# Filter.net
KiCad netlist of a schematic drawn in Altium Designer
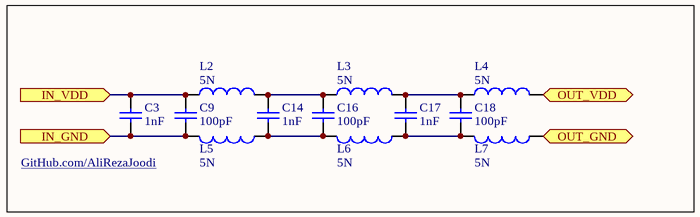
[diagram p0: Filter.SchDoc]

(export (version "E")
  (design (tool "Eeschema 10.0.6"))
  (components
    (comp (ref "C3")
      (value "1nF")
      (footprint "CAPNTO2.54-3.56x2.03")
      (description "Capacitor")
      (fields (field (name "MANUFACTURER") "Generic Components") (field (name "PUBLISHER") "Altium Limited"))
      (libsource (lib "Miscellaneous Devices") (part "Cap"))
    )
    (comp (ref "C9")
      (value "100pF")
      (footprint "CAPNTO2.54-3.56x2.03")
      (description "Capacitor")
      (fields (field (name "MANUFACTURER") "Generic Components") (field (name "PUBLISHER") "Altium Limited"))
      (libsource (lib "Miscellaneous Devices") (part "Cap"))
    )
    (comp (ref "C14")
      (value "1nF")
      (footprint "CAPNTO2.54-3.56x2.03")
      (description "Capacitor")
      (fields (field (name "MANUFACTURER") "Generic Components") (field (name "PUBLISHER") "Altium Limited"))
      (libsource (lib "Miscellaneous Devices") (part "Cap"))
    )
    (comp (ref "C16")
      (value "100pF")
      (footprint "CAPNTO2.54-3.56x2.03")
      (description "Capacitor")
      (fields (field (name "MANUFACTURER") "Generic Components") (field (name "PUBLISHER") "Altium Limited"))
      (libsource (lib "Miscellaneous Devices") (part "Cap"))
    )
    (comp (ref "C17")
      (value "1nF")
      (footprint "CAPNTO2.54-3.56x2.03")
      (description "Capacitor")
      (fields (field (name "MANUFACTURER") "Generic Components") (field (name "PUBLISHER") "Altium Limited"))
      (libsource (lib "Miscellaneous Devices") (part "Cap"))
    )
    (comp (ref "C18")
      (value "100pF")
      (footprint "CAPNTO2.54-3.56x2.03")
      (description "Capacitor")
      (fields (field (name "MANUFACTURER") "Generic Components") (field (name "PUBLISHER") "Altium Limited"))
      (libsource (lib "Miscellaneous Devices") (part "Cap"))
    )
    (comp (ref "L2")
      (value "5N")
      (footprint "CAPPR5-6.3x11")
      (description "Inductor")
      (fields (field (name "MANUFACTURER") "Generic Components") (field (name "PUBLISHER") "Altium Limited"))
      (libsource (lib "my Libraries") (part "Inductor"))
    )
    (comp (ref "L3")
      (value "5N")
      (footprint "CAPPR5-6.3x11")
      (description "Inductor")
      (fields (field (name "MANUFACTURER") "Generic Components") (field (name "PUBLISHER") "Altium Limited"))
      (libsource (lib "my Libraries") (part "Inductor"))
    )
    (comp (ref "L4")
      (value "5N")
      (footprint "CAPPR5-6.3x11")
      (description "Inductor")
      (fields (field (name "MANUFACTURER") "Generic Components") (field (name "PUBLISHER") "Altium Limited"))
      (libsource (lib "my Libraries") (part "Inductor"))
    )
    (comp (ref "L5")
      (value "5N")
      (footprint "CAPPR5-6.3x11")
      (description "Inductor")
      (fields (field (name "MANUFACTURER") "Generic Components") (field (name "PUBLISHER") "Altium Limited"))
      (libsource (lib "") (part "Inductor_1"))
    )
    (comp (ref "L6")
      (value "5N")
      (footprint "CAPPR5-6.3x11")
      (description "Inductor")
      (fields (field (name "MANUFACTURER") "Generic Components") (field (name "PUBLISHER") "Altium Limited"))
      (libsource (lib "") (part "Inductor_1"))
    )
    (comp (ref "L7")
      (value "5N")
      (footprint "CAPPR5-6.3x11")
      (description "Inductor")
      (fields (field (name "MANUFACTURER") "Generic Components") (field (name "PUBLISHER") "Altium Limited"))
      (libsource (lib "") (part "Inductor_1"))
    )
  )
  (nets
    (net (code "1") (name "/IN_GND") (class "Default")
      (node (ref "C3") (pin "1") (pinfunction "1_1") (pintype "passive"))
      (node (ref "C9") (pin "1") (pinfunction "1_1") (pintype "passive"))
      (node (ref "L5") (pin "2") (pinfunction "2_2") (pintype "passive"))
    )
    (net (code "2") (name "/IN_VDD") (class "Default")
      (node (ref "C3") (pin "2") (pinfunction "2_2") (pintype "passive"))
      (node (ref "C9") (pin "2") (pinfunction "2_2") (pintype "passive"))
      (node (ref "L2") (pin "2") (pinfunction "2_2") (pintype "passive"))
    )
    (net (code "3") (name "/OUT_GND") (class "Default")
      (node (ref "L7") (pin "1") (pinfunction "1_1") (pintype "passive"))
    )
    (net (code "4") (name "/OUT_VDD") (class "Default")
      (node (ref "L4") (pin "1") (pinfunction "1_1") (pintype "passive"))
    )
    (net (code "5") (name "Net-(C14-Pad1)") (class "Default")
      (node (ref "C14") (pin "1") (pinfunction "1_1") (pintype "passive"))
      (node (ref "C16") (pin "1") (pinfunction "1_1") (pintype "passive"))
      (node (ref "L5") (pin "1") (pinfunction "1_1") (pintype "passive"))
      (node (ref "L6") (pin "2") (pinfunction "2_2") (pintype "passive"))
    )
    (net (code "6") (name "Net-(C14-Pad2)") (class "Default")
      (node (ref "C14") (pin "2") (pinfunction "2_2") (pintype "passive"))
      (node (ref "C16") (pin "2") (pinfunction "2_2") (pintype "passive"))
      (node (ref "L2") (pin "1") (pinfunction "1_1") (pintype "passive"))
      (node (ref "L3") (pin "2") (pinfunction "2_2") (pintype "passive"))
    )
    (net (code "7") (name "Net-(C17-Pad1)") (class "Default")
      (node (ref "C17") (pin "1") (pinfunction "1_1") (pintype "passive"))
      (node (ref "C18") (pin "1") (pinfunction "1_1") (pintype "passive"))
      (node (ref "L6") (pin "1") (pinfunction "1_1") (pintype "passive"))
      (node (ref "L7") (pin "2") (pinfunction "2_2") (pintype "passive"))
    )
    (net (code "8") (name "Net-(C17-Pad2)") (class "Default")
      (node (ref "C17") (pin "2") (pinfunction "2_2") (pintype "passive"))
      (node (ref "C18") (pin "2") (pinfunction "2_2") (pintype "passive"))
      (node (ref "L3") (pin "1") (pinfunction "1_1") (pintype "passive"))
      (node (ref "L4") (pin "2") (pinfunction "2_2") (pintype "passive"))
    )
  )
)
